# 3_Bias_Supply.net
KiCad netlist of a schematic drawn in Altium Designer
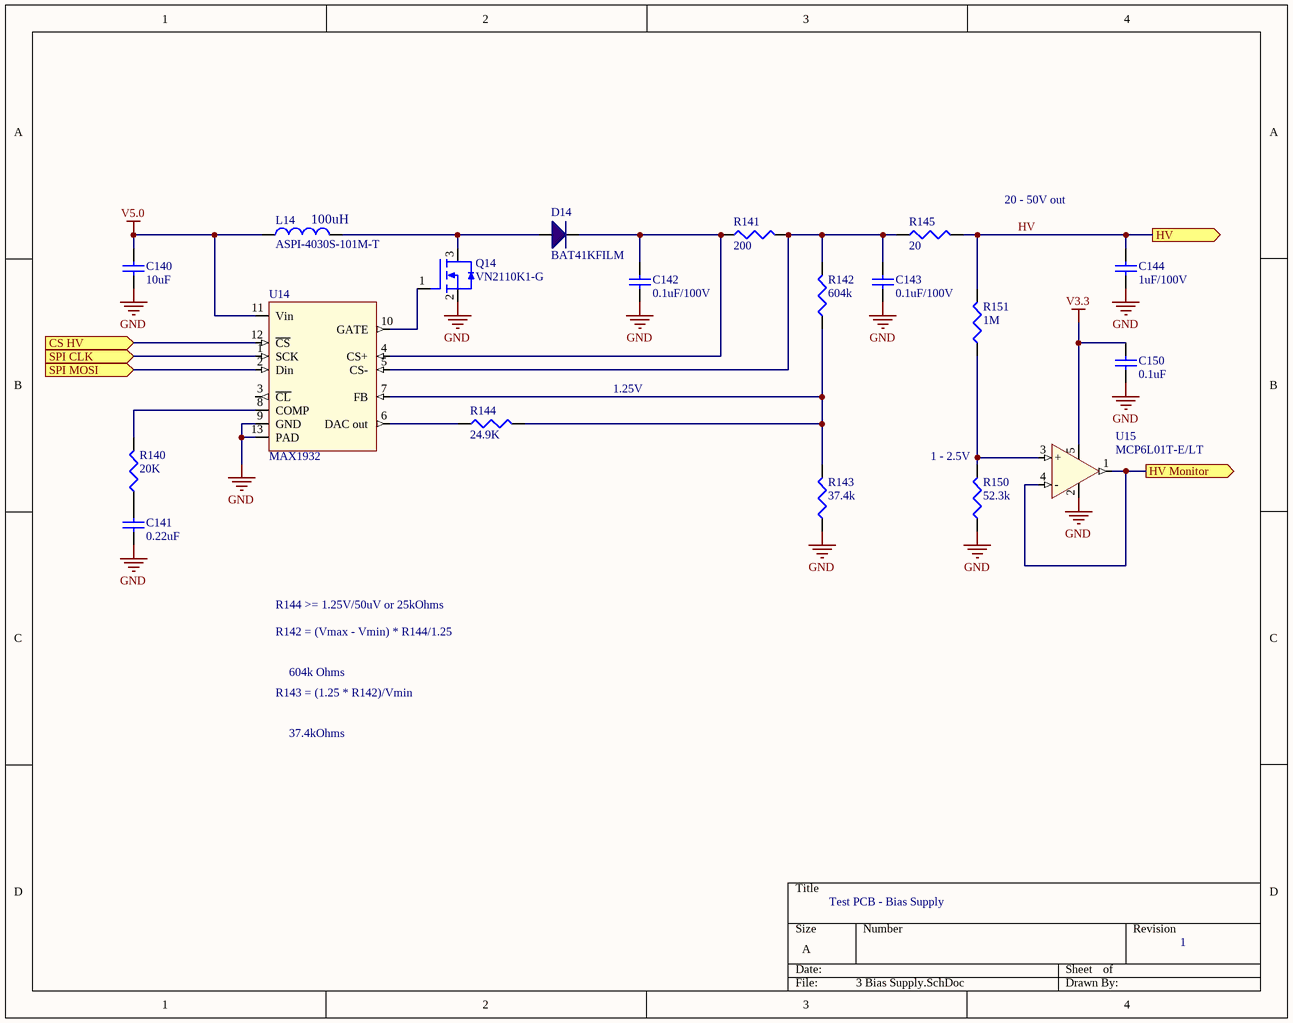
[diagram p0: 3 Bias Supply.SchDoc]

(export (version "E")
  (design (tool "Eeschema 10.0.6"))
  (components
    (comp (ref "C140")
      (value "10uF")
      (footprint "C0805")
      (description "Capacitor, SM")
      (fields (field (name "PUBLISHER") "Altium Limited"))
      (libsource (lib "Graylark") (part "Cap SM"))
    )
    (comp (ref "C141")
      (value "0.22uF")
      (footprint "C0603")
      (description "Capacitor, SM")
      (fields (field (name "PUBLISHER") "Altium Limited"))
      (libsource (lib "Graylark") (part "Cap SM"))
    )
    (comp (ref "C142")
      (value "0.1uF/100V")
      (footprint "C0603")
      (description "Capacitor, SM")
      (fields (field (name "PUBLISHER") "Altium Limited"))
      (libsource (lib "Graylark") (part "Cap SM"))
    )
    (comp (ref "C143")
      (value "0.1uF/100V")
      (footprint "C0603")
      (description "Capacitor, SM")
      (fields (field (name "PUBLISHER") "Altium Limited"))
      (libsource (lib "Graylark") (part "Cap SM"))
    )
    (comp (ref "C144")
      (value "1uF/100V")
      (footprint "C0805")
      (description "Capacitor, SM")
      (fields (field (name "PUBLISHER") "Altium Limited"))
      (libsource (lib "Graylark") (part "Cap SM"))
    )
    (comp (ref "C150")
      (value "0.1uF")
      (footprint "C0402")
      (description "Capacitor, SM")
      (fields (field (name "PUBLISHER") "Altium Limited"))
      (libsource (lib "Graylark") (part "Cap SM"))
    )
    (comp (ref "D14")
      (value "BAT41KFILM")
      (footprint "SOD523")
      (description "Schottky diode")
      (libsource (lib "Graylark") (part "BAT41KFILM"))
    )
    (comp (ref "L14")
      (value "ASPI-4030S-101M-T")
      (footprint "L_4018")
      (description "47uH inductor")
      (fields (field (name "INDUCTANCE") "100uH"))
      (libsource (lib "Graylark") (part "Inductor"))
    )
    (comp (ref "Q14")
      (value "VN2110K1-G")
      (footprint "SOT23-3")
      (description "N FET")
      (fields (field (name "PART NUMBER") "DMN10H220L-7"))
      (libsource (lib "Graylark") (part "N FET"))
    )
    (comp (ref "R140")
      (value "20K")
      (footprint "R0603")
      (description "Resistor")
      (fields (field (name "PUBLISHER") "Altium Limited"))
      (libsource (lib "Graylark") (part "Res SM"))
    )
    (comp (ref "R141")
      (value "200")
      (footprint "R0603")
      (description "Resistor")
      (fields (field (name "PUBLISHER") "Altium Limited"))
      (libsource (lib "Graylark") (part "Res SM"))
    )
    (comp (ref "R142")
      (value "604k")
      (footprint "R0603")
      (description "Resistor")
      (fields (field (name "PUBLISHER") "Altium Limited"))
      (libsource (lib "Graylark") (part "Res SM"))
    )
    (comp (ref "R143")
      (value "37.4k")
      (footprint "R0603")
      (description "Resistor")
      (fields (field (name "PUBLISHER") "Altium Limited"))
      (libsource (lib "Graylark") (part "Res SM"))
    )
    (comp (ref "R144")
      (value "24.9K")
      (footprint "R0603")
      (description "Resistor")
      (fields (field (name "PUBLISHER") "Altium Limited"))
      (libsource (lib "Graylark") (part "Res SM"))
    )
    (comp (ref "R145")
      (value "20")
      (footprint "R0603")
      (description "Resistor")
      (fields (field (name "PUBLISHER") "Altium Limited"))
      (libsource (lib "Graylark") (part "Res SM"))
    )
    (comp (ref "R150")
      (value "52.3k")
      (footprint "R0603")
      (description "Resistor")
      (fields (field (name "PUBLISHER") "Altium Limited"))
      (libsource (lib "Graylark") (part "Res SM"))
    )
    (comp (ref "R151")
      (value "1M")
      (footprint "R0603")
      (description "Resistor")
      (fields (field (name "PUBLISHER") "Altium Limited"))
      (libsource (lib "Graylark") (part "Res SM"))
    )
    (comp (ref "U14")
      (value "MAX1932")
      (footprint "QFN127P600-12N")
      (description "APD bias supply")
      (libsource (lib "Graylark") (part "MAX1932"))
    )
    (comp (ref "U15")
      (value "MCP6L01T-E/LT")
      (footprint "SOT23-5")
      (description "Op amp RRIO")
      (libsource (lib "Graylark") (part "MCP6L01"))
    )
  )
  (nets
    (net (code "1") (name "/CS HV") (class "Default")
      (node (ref "U14") (pin "12") (pinfunction "~{CS}_12") (pintype "input"))
    )
    (net (code "2") (name "/HV") (class "Default")
      (node (ref "C144") (pin "2") (pinfunction "2_2") (pintype "passive"))
      (node (ref "R145") (pin "2") (pinfunction "2_2") (pintype "passive"))
      (node (ref "R151") (pin "2") (pinfunction "2_2") (pintype "passive"))
    )
    (net (code "3") (name "/HV Monitor") (class "Default")
      (node (ref "U15") (pin "1") (pinfunction "Vout_1") (pintype "output"))
      (node (ref "U15") (pin "4") (pinfunction "-_4") (pintype "input"))
    )
    (net (code "4") (name "/SPI CLK") (class "Default")
      (node (ref "U14") (pin "1") (pinfunction "SCK_1") (pintype "input"))
    )
    (net (code "5") (name "/SPI MOSI") (class "Default")
      (node (ref "U14") (pin "2") (pinfunction "Din_2") (pintype "input"))
    )
    (net (code "6") (name "GND") (class "Default")
      (node (ref "C140") (pin "1") (pinfunction "1_1") (pintype "passive"))
      (node (ref "C141") (pin "1") (pinfunction "1_1") (pintype "passive"))
      (node (ref "C142") (pin "1") (pinfunction "1_1") (pintype "passive"))
      (node (ref "C143") (pin "1") (pinfunction "1_1") (pintype "passive"))
      (node (ref "C144") (pin "1") (pinfunction "1_1") (pintype "passive"))
      (node (ref "C150") (pin "1") (pinfunction "1_1") (pintype "passive"))
      (node (ref "Q14") (pin "2") (pinfunction "2_2") (pintype "passive"))
      (node (ref "R143") (pin "1") (pinfunction "1_1") (pintype "passive"))
      (node (ref "R150") (pin "1") (pinfunction "1_1") (pintype "passive"))
      (node (ref "U14") (pin "13") (pinfunction "PAD_13") (pintype "passive"))
      (node (ref "U14") (pin "9") (pinfunction "GND_9") (pintype "power_in"))
      (node (ref "U15") (pin "2") (pinfunction "GND_2") (pintype "power_in"))
    )
    (net (code "7") (name "Net-(C141-Pad2)") (class "Default")
      (node (ref "C141") (pin "2") (pinfunction "2_2") (pintype "passive"))
      (node (ref "R140") (pin "1") (pinfunction "1_1") (pintype "passive"))
    )
    (net (code "8") (name "Net-(D14-A)") (class "Default")
      (node (ref "D14") (pin "1") (pinfunction "A_1") (pintype "passive"))
      (node (ref "L14") (pin "2") (pinfunction "2_2") (pintype "passive"))
      (node (ref "Q14") (pin "3") (pinfunction "3_3") (pintype "passive"))
    )
    (net (code "9") (name "Net-(D14-K)") (class "Default")
      (node (ref "C142") (pin "2") (pinfunction "2_2") (pintype "passive"))
      (node (ref "D14") (pin "2") (pinfunction "K_2") (pintype "passive"))
      (node (ref "R141") (pin "1") (pinfunction "1_1") (pintype "passive"))
      (node (ref "U14") (pin "4") (pinfunction "CS+_4") (pintype "input"))
    )
    (net (code "10") (name "Net-(U14-COMP)") (class "Default")
      (node (ref "R140") (pin "2") (pinfunction "2_2") (pintype "passive"))
      (node (ref "U14") (pin "8") (pinfunction "COMP_8") (pintype "passive"))
    )
    (net (code "11") (name "Net-(U14-CS-)") (class "Default")
      (node (ref "C143") (pin "2") (pinfunction "2_2") (pintype "passive"))
      (node (ref "R141") (pin "2") (pinfunction "2_2") (pintype "passive"))
      (node (ref "R142") (pin "2") (pinfunction "2_2") (pintype "passive"))
      (node (ref "R145") (pin "1") (pinfunction "1_1") (pintype "passive"))
      (node (ref "U14") (pin "5") (pinfunction "CS-_5") (pintype "input"))
    )
    (net (code "12") (name "Net-(U14-DAC_out)") (class "Default")
      (node (ref "R144") (pin "1") (pinfunction "1_1") (pintype "passive"))
      (node (ref "U14") (pin "6") (pinfunction "DAC_out_6") (pintype "output"))
    )
    (net (code "13") (name "Net-(U14-FB)") (class "Default")
      (node (ref "R142") (pin "1") (pinfunction "1_1") (pintype "passive"))
      (node (ref "R143") (pin "2") (pinfunction "2_2") (pintype "passive"))
      (node (ref "R144") (pin "2") (pinfunction "2_2") (pintype "passive"))
      (node (ref "U14") (pin "7") (pinfunction "FB_7") (pintype "input"))
    )
    (net (code "14") (name "Net-(U14-GATE)") (class "Default")
      (node (ref "Q14") (pin "1") (pinfunction "1_1") (pintype "passive"))
      (node (ref "U14") (pin "10") (pinfunction "GATE_10") (pintype "output"))
    )
    (net (code "15") (name "Net-(U15-+)") (class "Default")
      (node (ref "R150") (pin "2") (pinfunction "2_2") (pintype "passive"))
      (node (ref "R151") (pin "1") (pinfunction "1_1") (pintype "passive"))
      (node (ref "U15") (pin "3") (pinfunction "+_3") (pintype "input"))
    )
    (net (code "16") (name "V3.3") (class "Default")
      (node (ref "C150") (pin "2") (pinfunction "2_2") (pintype "passive"))
      (node (ref "U15") (pin "5") (pinfunction "Vdd_5") (pintype "power_in"))
    )
    (net (code "17") (name "V5.0") (class "Default")
      (node (ref "C140") (pin "2") (pinfunction "2_2") (pintype "passive"))
      (node (ref "L14") (pin "1") (pinfunction "1_1") (pintype "passive"))
      (node (ref "U14") (pin "11") (pinfunction "Vin_11") (pintype "power_in"))
    )
    (net (code "18") (name "unconnected-(U14-~{CL}-Pad3)") (class "Default")
      (node (ref "U14") (pin "3") (pinfunction "~{CL}_3") (pintype "output"))
    )
  )
)
